# cmt2300a_olimex.net
KiCad netlist of a schematic drawn in EAGLE
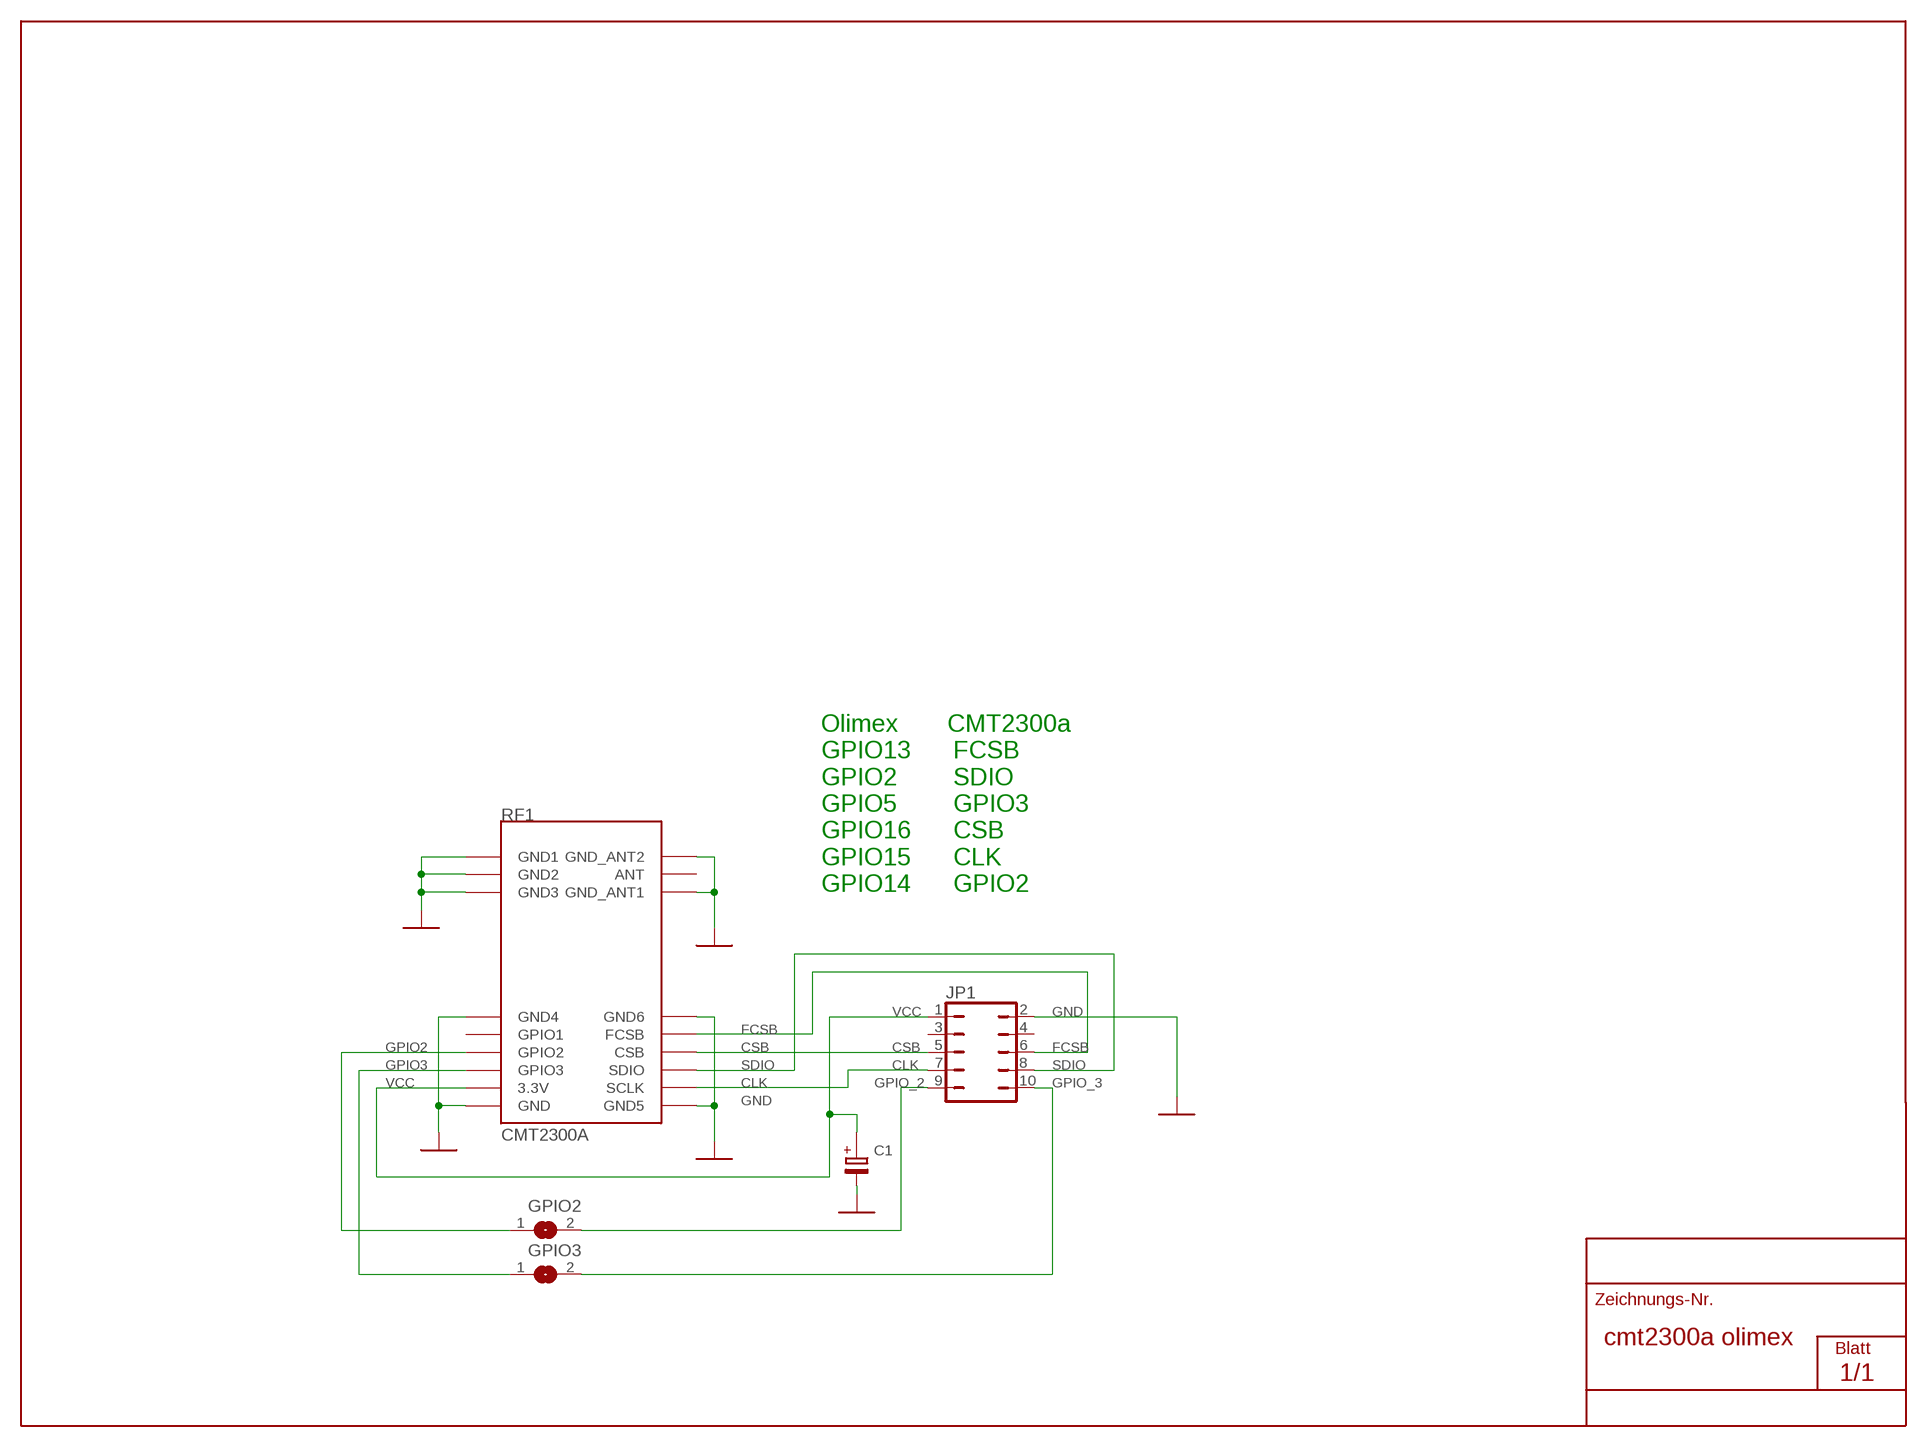
[diagram p0: schematic, sheet 1]

(export (version "E")
  (design (tool "Eeschema 10.0.6"))
  (components
    (comp (ref "C1")
      (value "S470µ/16")
      (footprint "eagle-import:EB10D")
      (libsource (lib "eagle-import") (part "S470µ/16"))
    )
    (comp (ref "GPIO2")
      (value "SJ")
      (footprint "eagle-import:SJ")
      (libsource (lib "eagle-import") (part "SJ"))
    )
    (comp (ref "GPIO3")
      (value "SJ")
      (footprint "eagle-import:SJ")
      (libsource (lib "eagle-import") (part "SJ"))
    )
    (comp (ref "JP1")
      (value "JP5Q_OT")
      (footprint "eagle-import:JP5Q_OT")
      (libsource (lib "eagle-import") (part "JP5Q_OT"))
    )
    (comp (ref "RF1")
      (value "CMT2300A")
      (footprint "eagle-import:CMT2300A")
      (libsource (lib "eagle-import") (part "CMT2300A"))
    )
  )
  (nets
    (net (code "1") (name "/CLK") (class "Default")
      (node (ref "JP1") (pin "7") (pinfunction "7_7") (pintype "passive"))
      (node (ref "RF1") (pin "SCLK") (pinfunction "SCLK_SCLK") (pintype "bidirectional"))
    )
    (net (code "2") (name "/CSB") (class "Default")
      (node (ref "JP1") (pin "5") (pinfunction "5_5") (pintype "passive"))
      (node (ref "RF1") (pin "CSB") (pinfunction "CSB_CSB") (pintype "bidirectional"))
    )
    (net (code "3") (name "/FCSB") (class "Default")
      (node (ref "JP1") (pin "6") (pinfunction "6_6") (pintype "passive"))
      (node (ref "RF1") (pin "FCSB") (pinfunction "FCSB_FCSB") (pintype "bidirectional"))
    )
    (net (code "4") (name "/GPIO2") (class "Default")
      (node (ref "GPIO2") (pin "1") (pinfunction "1_1") (pintype "passive"))
      (node (ref "RF1") (pin "GPIO2") (pinfunction "GPIO2_GPIO2") (pintype "bidirectional"))
    )
    (net (code "5") (name "/GPIO3") (class "Default")
      (node (ref "GPIO3") (pin "1") (pinfunction "1_1") (pintype "passive"))
      (node (ref "RF1") (pin "GPIO3") (pinfunction "GPIO3_GPIO3") (pintype "bidirectional"))
    )
    (net (code "6") (name "/GPIO_2") (class "Default")
      (node (ref "GPIO2") (pin "2") (pinfunction "2_2") (pintype "passive"))
      (node (ref "JP1") (pin "9") (pinfunction "9_9") (pintype "passive"))
    )
    (net (code "7") (name "/GPIO_3") (class "Default")
      (node (ref "GPIO3") (pin "2") (pinfunction "2_2") (pintype "passive"))
      (node (ref "JP1") (pin "10") (pinfunction "10_10") (pintype "passive"))
    )
    (net (code "8") (name "/SDIO") (class "Default")
      (node (ref "JP1") (pin "8") (pinfunction "8_8") (pintype "passive"))
      (node (ref "RF1") (pin "SDIO") (pinfunction "SDIO_SDIO") (pintype "bidirectional"))
    )
    (net (code "9") (name "/VCC") (class "Default")
      (node (ref "C1") (pin "+") (pinfunction "+_+") (pintype "passive"))
      (node (ref "JP1") (pin "1") (pinfunction "1_1") (pintype "passive"))
      (node (ref "RF1") (pin "3.3V") (pinfunction "3.3V_3.3V") (pintype "bidirectional"))
    )
    (net (code "10") (name "GND") (class "Default")
      (node (ref "C1") (pin "-") (pinfunction "-_-") (pintype "passive"))
      (node (ref "JP1") (pin "2") (pinfunction "2_2") (pintype "passive"))
      (node (ref "RF1") (pin "GND") (pinfunction "GND_GND") (pintype "bidirectional"))
      (node (ref "RF1") (pin "GND1") (pinfunction "GND1_GND1") (pintype "bidirectional"))
      (node (ref "RF1") (pin "GND2") (pinfunction "GND2_GND2") (pintype "bidirectional"))
      (node (ref "RF1") (pin "GND3") (pinfunction "GND3_GND3") (pintype "bidirectional"))
      (node (ref "RF1") (pin "GND4") (pinfunction "GND4_GND4") (pintype "bidirectional"))
      (node (ref "RF1") (pin "GND5") (pinfunction "GND5_GND5") (pintype "bidirectional"))
      (node (ref "RF1") (pin "GND6") (pinfunction "GND6_GND6") (pintype "bidirectional"))
      (node (ref "RF1") (pin "GND_ANT1") (pinfunction "GND_ANT1_GND_ANT1") (pintype "bidirectional"))
      (node (ref "RF1") (pin "GND_ANT2") (pinfunction "GND_ANT2_GND_ANT2") (pintype "bidirectional"))
    )
    (net (code "11") (name "unconnected-(JP1-Pad3)") (class "Default")
      (node (ref "JP1") (pin "3") (pinfunction "3_3") (pintype "passive"))
    )
    (net (code "12") (name "unconnected-(JP1-Pad4)") (class "Default")
      (node (ref "JP1") (pin "4") (pinfunction "4_4") (pintype "passive"))
    )
    (net (code "13") (name "unconnected-(RF1-PadANT)") (class "Default")
      (node (ref "RF1") (pin "ANT") (pinfunction "ANT_ANT") (pintype "bidirectional"))
    )
    (net (code "14") (name "unconnected-(RF1-PadGPIO1)") (class "Default")
      (node (ref "RF1") (pin "GPIO1") (pinfunction "GPIO1_GPIO1") (pintype "bidirectional"))
    )
  )
)
